# tank.net
KiCad netlist of a schematic drawn in EAGLE
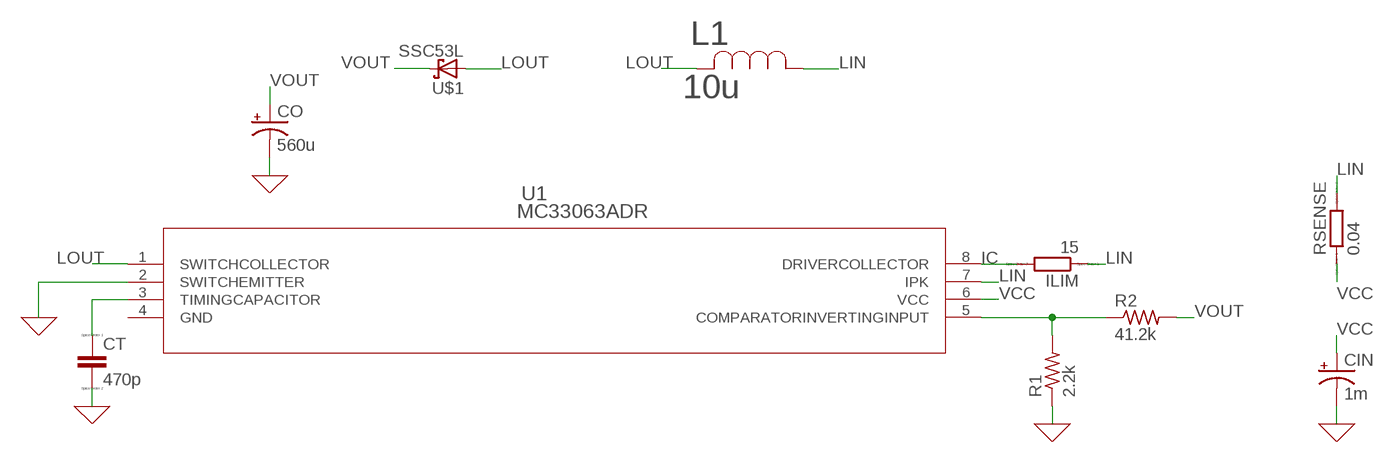
[diagram p0: schematic, sheet 1]

(export (version "E")
  (design (tool "Eeschema 10.0.6"))
  (components
    (comp (ref "CIN")
      (value "1m")
      (footprint "eagle-import:E3,5-10")
      (fields (field (name "MANUFACTURER_PART_NUMBER") "ECA-1EM102"))
      (libsource (lib "eagle-import") (part "CPOL-USE3.5-10"))
    )
    (comp (ref "CO")
      (value "560u")
      (footprint "eagle-import:E5-13")
      (fields (field (name "MANUFACTURER_PART_NUMBER") "EEU-FC1V561S"))
      (libsource (lib "eagle-import") (part "CPOL-USE5-13"))
    )
    (comp (ref "CT")
      (value "470p")
      (footprint "eagle-import:C0402")
      (fields (field (name "MANUFACTURER_PART_NUMBER") "GRM155R71H471KA01D"))
      (libsource (lib "eagle-import") (part "CC0402"))
    )
    (comp (ref "ILIM")
      (value "15")
      (footprint "eagle-import:R0603")
      (fields (field (name "MANUFACTURER_PART_NUMBER") "CSRN2010FK40L0CT-ND"))
      (libsource (lib "eagle-import") (part "RR0603"))
    )
    (comp (ref "L1")
      (value "10u")
      (footprint "eagle-import:AIUR-06")
      (fields (field (name "MANUFACTURER_PART_NUMBER") "AIUR06100K"))
      (libsource (lib "eagle-import") (part "AIUR-06-100K"))
    )
    (comp (ref "R1")
      (value "2.2k")
      (footprint "eagle-import:R0402")
      (fields (field (name "MANUFACTURER_PART_NUMBER") "ERJ-2RKF2201X"))
      (libsource (lib "eagle-import") (part "R-US_R0402"))
    )
    (comp (ref "R2")
      (value "41.2k")
      (footprint "eagle-import:R0805")
      (fields (field (name "MANUFACTURER_PART_NUMBER") "RC0805FR-0741K2L"))
      (libsource (lib "eagle-import") (part "R-US_R0805"))
    )
    (comp (ref "RSENSE")
      (value "0.04")
      (footprint "eagle-import:R2010")
      (fields (field (name "MANUFACTURER_PART_NUMBER") "CSRN2010FK40L0CT-ND"))
      (libsource (lib "eagle-import") (part "RR2010"))
    )
    (comp (ref "U$1")
      (value "SSC53L")
      (footprint "eagle-import:DO-214AB")
      (fields (field (name "MANUFACTURER_PART_NUMBER") "SSC53L-E3/57T"))
      (libsource (lib "eagle-import") (part "SSC53L"))
    )
    (comp (ref "U1")
      (value "MC33063ADR")
      (footprint "eagle-import:D8")
      (libsource (lib "eagle-import") (part "MC33063ADR"))
    )
  )
  (nets
    (net (code "1") (name "/IC") (class "Default")
      (node (ref "ILIM") (pin "2") (pinfunction "2_2") (pintype "passive"))
      (node (ref "U1") (pin "8") (pinfunction "DRIVERCOLLECTOR_8") (pintype "passive"))
    )
    (net (code "2") (name "/LIN") (class "Default")
      (node (ref "ILIM") (pin "1") (pinfunction "1_1") (pintype "passive"))
      (node (ref "L1") (pin "1") (pinfunction "1_1") (pintype "passive"))
      (node (ref "RSENSE") (pin "2") (pinfunction "2_2") (pintype "passive"))
      (node (ref "U1") (pin "7") (pinfunction "IPK_7") (pintype "passive"))
    )
    (net (code "3") (name "/LOUT") (class "Default")
      (node (ref "L1") (pin "2") (pinfunction "2_2") (pintype "passive"))
      (node (ref "U$1") (pin "2") (pinfunction "A_2") (pintype "passive"))
      (node (ref "U1") (pin "1") (pinfunction "SWITCHCOLLECTOR_1") (pintype "passive"))
    )
    (net (code "4") (name "/VCC") (class "Default")
      (node (ref "CIN") (pin "+") (pinfunction "+_+") (pintype "passive"))
      (node (ref "RSENSE") (pin "1") (pinfunction "1_1") (pintype "passive"))
      (node (ref "U1") (pin "6") (pinfunction "VCC_6") (pintype "passive"))
    )
    (net (code "5") (name "/VOUT") (class "Default")
      (node (ref "CO") (pin "+") (pinfunction "+_+") (pintype "passive"))
      (node (ref "R2") (pin "2") (pinfunction "2_2") (pintype "passive"))
      (node (ref "U$1") (pin "1") (pinfunction "C_1") (pintype "passive"))
    )
    (net (code "6") (name "GND") (class "Default")
      (node (ref "CIN") (pin "-") (pinfunction "-_-") (pintype "passive"))
      (node (ref "CO") (pin "-") (pinfunction "-_-") (pintype "passive"))
      (node (ref "CT") (pin "2") (pinfunction "2_2") (pintype "passive"))
      (node (ref "R1") (pin "1") (pinfunction "1_1") (pintype "passive"))
      (node (ref "U1") (pin "2") (pinfunction "SWITCHEMITTER_2") (pintype "passive"))
    )
    (net (code "7") (name "Net-(U1-COMPARATORINVERTINGINPUT)") (class "Default")
      (node (ref "R1") (pin "2") (pinfunction "2_2") (pintype "passive"))
      (node (ref "R2") (pin "1") (pinfunction "1_1") (pintype "passive"))
      (node (ref "U1") (pin "5") (pinfunction "COMPARATORINVERTINGINPUT_5") (pintype "passive"))
    )
    (net (code "8") (name "Net-(U1-TIMINGCAPACITOR)") (class "Default")
      (node (ref "CT") (pin "1") (pinfunction "1_1") (pintype "passive"))
      (node (ref "U1") (pin "3") (pinfunction "TIMINGCAPACITOR_3") (pintype "passive"))
    )
    (net (code "9") (name "unconnected-(U1-GND-Pad4)") (class "Default")
      (node (ref "U1") (pin "4") (pinfunction "GND_4") (pintype "passive"))
    )
  )
)
